# EvoProject_1_0_-_Entradas_e_Sa_das.net
KiCad netlist of a schematic drawn in Altium Designer
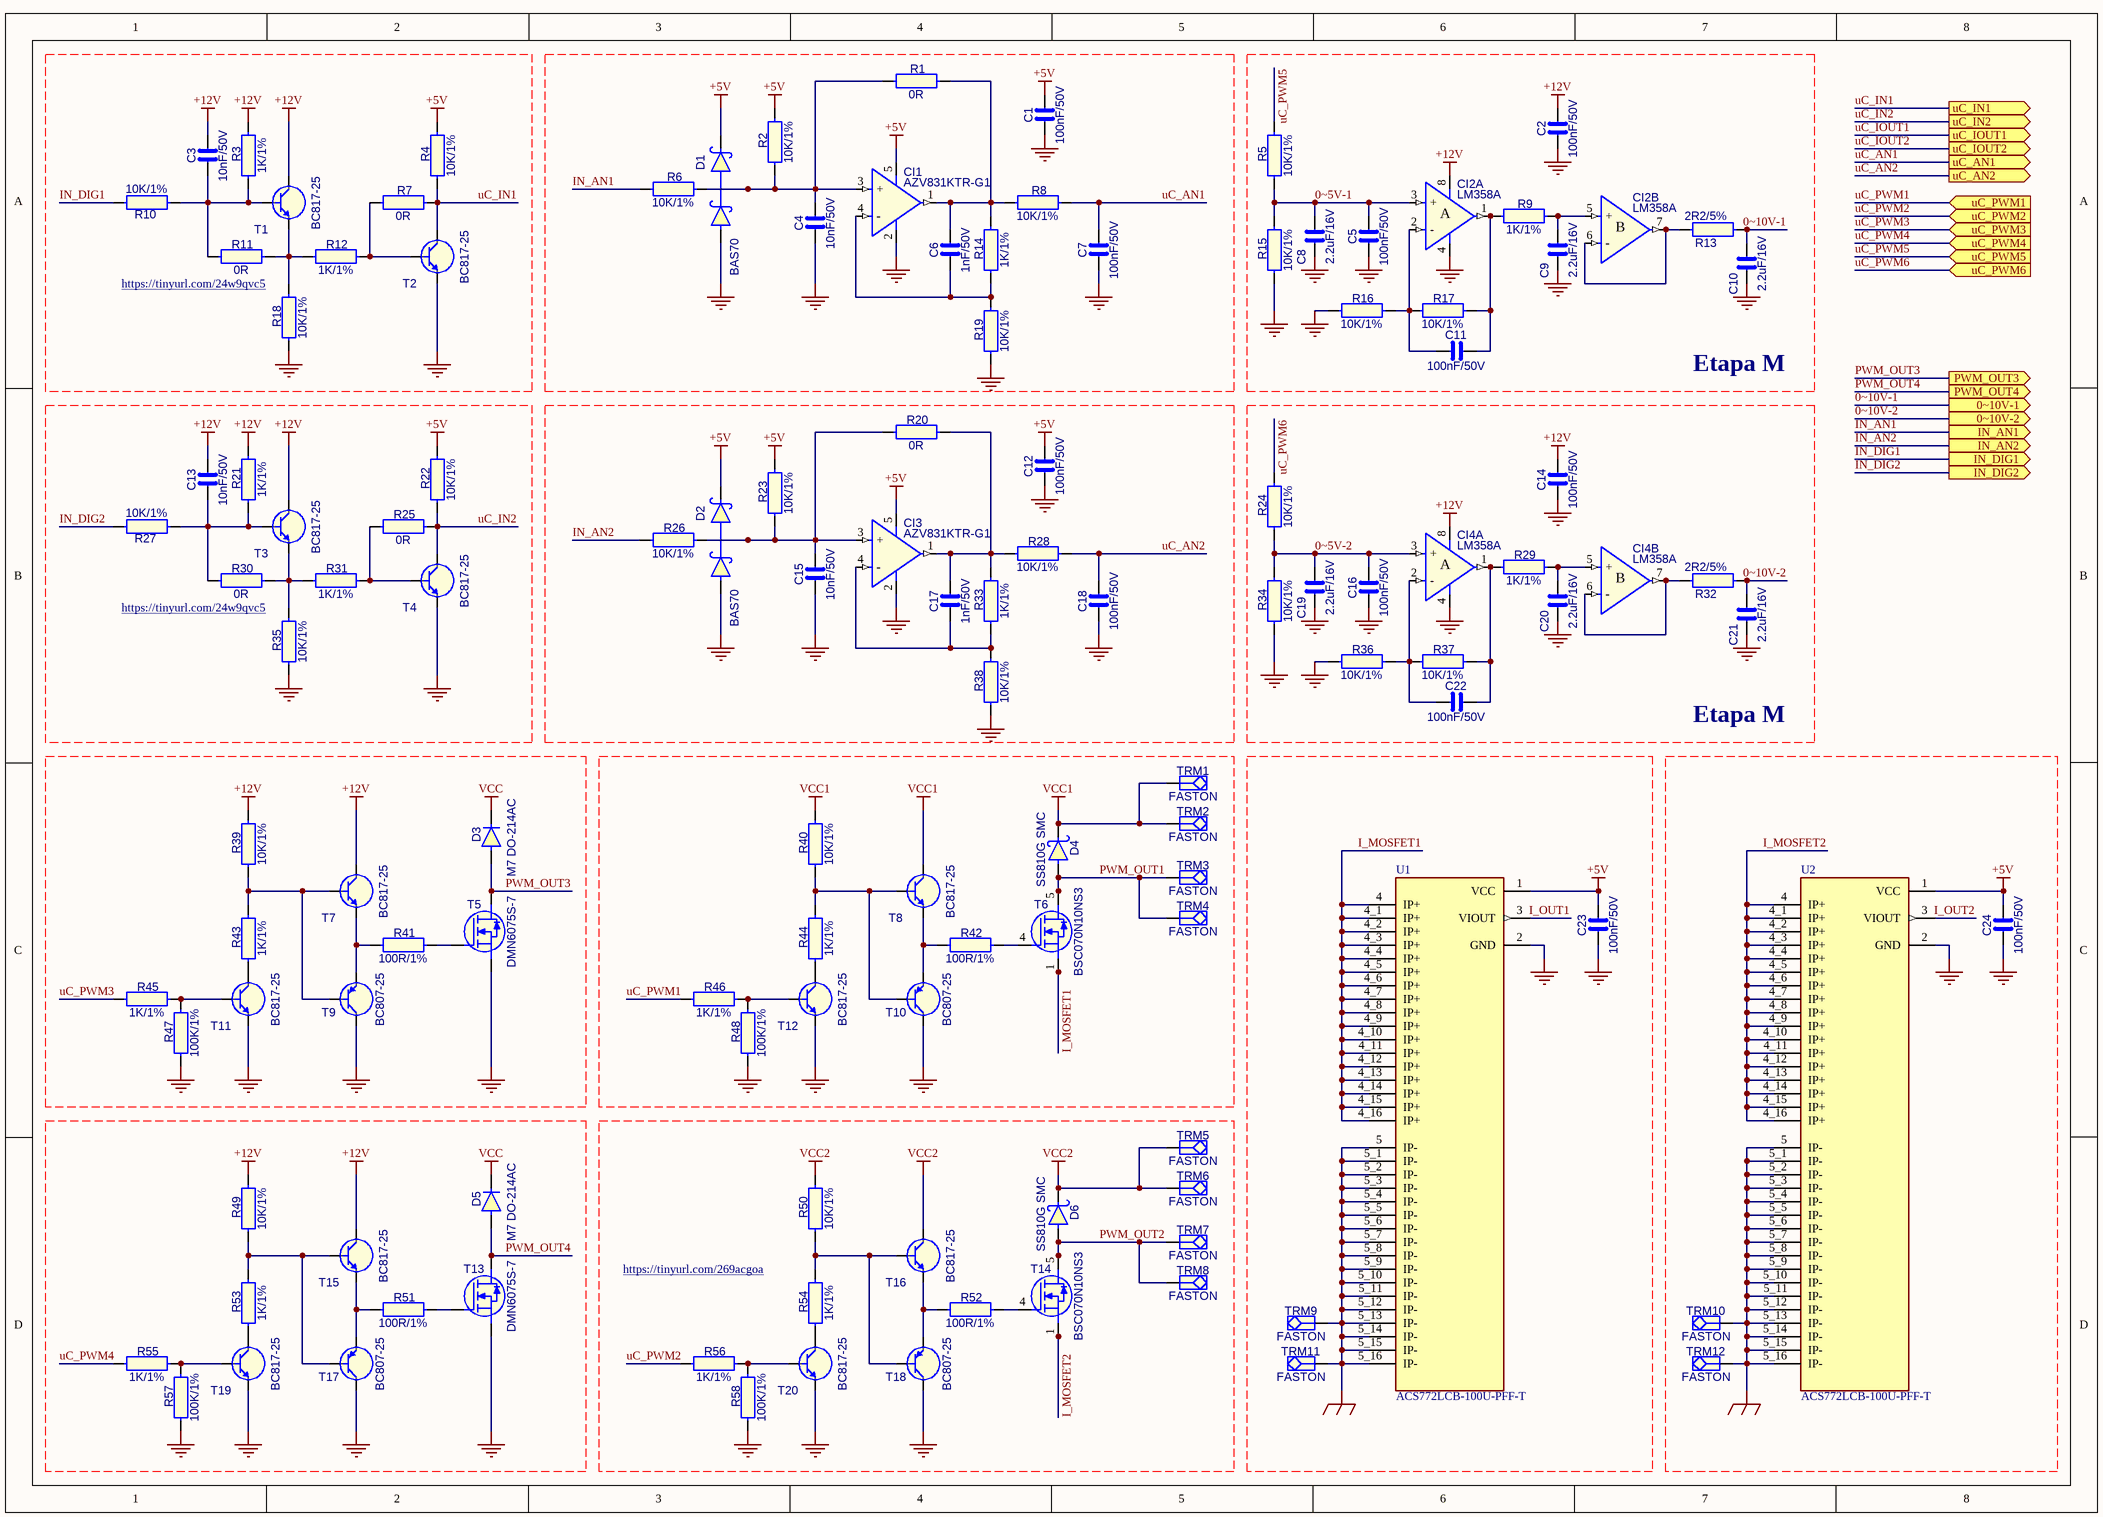
[diagram p0: EvoProject 1.0 - Entradas e Saídas.SchDoc]

(export (version "E")
  (design (tool "Eeschema 10.0.6"))
  (components
    (comp (ref "C1")
      (value "100nF/50V")
      (footprint "CAP SMD CE 0603 HR")
      (description "CAPACITOR SMD CE 0603 100nF 50V 10% X7R")
      (libsource (lib "INOVA SISTEMAS ELETRONICOS") (part "CAP_NP"))
    )
    (comp (ref "C2")
      (value "100nF/50V")
      (footprint "CAP SMD CE 0603 HR")
      (description "CAPACITOR SMD CE 0603 100nF 50V 10% X7R")
      (libsource (lib "INOVA SISTEMAS ELETRONICOS") (part "CAP_NP"))
    )
    (comp (ref "C3")
      (value "10nF/50V")
      (footprint "CAP SMD CE 0603 HR")
      (description "CAPACITOR SMD CE 0603 10nF 50V 20% X7R")
      (libsource (lib "INOVA SISTEMAS ELETRONICOS") (part "CAP_NP"))
    )
    (comp (ref "C4")
      (value "10nF/50V")
      (footprint "CAP SMD CE 0603 HR")
      (description "CAPACITOR SMD CE 0603 10nF 50V 20% X7R")
      (libsource (lib "INOVA SISTEMAS ELETRONICOS") (part "CAP_NP"))
    )
    (comp (ref "C5")
      (value "100nF/50V")
      (footprint "CAP SMD CE 0603 HR")
      (description "CAPACITOR SMD CE 0603 100nF 50V 10% X7R")
      (libsource (lib "INOVA SISTEMAS ELETRONICOS") (part "CAP_NP"))
    )
    (comp (ref "C6")
      (value "1nF/50V")
      (footprint "CAP SMD CE 0603 HR")
      (description "CAPACITOR SMD CE 0603 1nF 50V 10% X7R")
      (libsource (lib "INOVA SISTEMAS ELETRONICOS") (part "CAP_NP"))
    )
    (comp (ref "C7")
      (value "100nF/50V")
      (footprint "CAP SMD CE 0603 HR")
      (description "CAPACITOR SMD CE 0603 100nF 50V 10% X7R")
      (libsource (lib "INOVA SISTEMAS ELETRONICOS") (part "CAP_NP"))
    )
    (comp (ref "C8")
      (value "2.2uF/16V")
      (footprint "CAP SMD CE 0603 HR")
      (description "CAPACITOR SMD CE 0603 2,2uF 16V 10% X5R")
      (libsource (lib "INOVA SISTEMAS ELETRONICOS") (part "CAP_NP"))
    )
    (comp (ref "C9")
      (value "2.2uF/16V")
      (footprint "CAP SMD CE 0603 HR")
      (description "CAPACITOR SMD CE 0603 2,2uF 16V 10% X5R")
      (libsource (lib "INOVA SISTEMAS ELETRONICOS") (part "CAP_NP"))
    )
    (comp (ref "C10")
      (value "2.2uF/16V")
      (footprint "CAP SMD CE 0603 HR")
      (description "CAPACITOR SMD CE 0603 2,2uF 16V 10% X5R")
      (libsource (lib "INOVA SISTEMAS ELETRONICOS") (part "CAP_NP"))
    )
    (comp (ref "C11")
      (value "100nF/50V")
      (footprint "CAP SMD CE 0603 HR")
      (description "CAPACITOR SMD CE 0603 100nF 50V 10% X7R")
      (libsource (lib "INOVA SISTEMAS ELETRONICOS") (part "CAP_NP"))
    )
    (comp (ref "C12")
      (value "100nF/50V")
      (footprint "CAP SMD CE 0603 HR")
      (description "CAPACITOR SMD CE 0603 100nF 50V 10% X7R")
      (libsource (lib "INOVA SISTEMAS ELETRONICOS") (part "CAP_NP"))
    )
    (comp (ref "C13")
      (value "10nF/50V")
      (footprint "CAP SMD CE 0603 HR")
      (description "CAPACITOR SMD CE 0603 10nF 50V 20% X7R")
      (libsource (lib "INOVA SISTEMAS ELETRONICOS") (part "CAP_NP"))
    )
    (comp (ref "C14")
      (value "100nF/50V")
      (footprint "CAP SMD CE 0603 HR")
      (description "CAPACITOR SMD CE 0603 100nF 50V 10% X7R")
      (libsource (lib "INOVA SISTEMAS ELETRONICOS") (part "CAP_NP"))
    )
    (comp (ref "C15")
      (value "10nF/50V")
      (footprint "CAP SMD CE 0603 HR")
      (description "CAPACITOR SMD CE 0603 10nF 50V 20% X7R")
      (libsource (lib "INOVA SISTEMAS ELETRONICOS") (part "CAP_NP"))
    )
    (comp (ref "C16")
      (value "100nF/50V")
      (footprint "CAP SMD CE 0603 HR")
      (description "CAPACITOR SMD CE 0603 100nF 50V 10% X7R")
      (libsource (lib "INOVA SISTEMAS ELETRONICOS") (part "CAP_NP"))
    )
    (comp (ref "C17")
      (value "1nF/50V")
      (footprint "CAP SMD CE 0603 HR")
      (description "CAPACITOR SMD CE 0603 1nF 50V 10% X7R")
      (libsource (lib "INOVA SISTEMAS ELETRONICOS") (part "CAP_NP"))
    )
    (comp (ref "C18")
      (value "100nF/50V")
      (footprint "CAP SMD CE 0603 HR")
      (description "CAPACITOR SMD CE 0603 100nF 50V 10% X7R")
      (libsource (lib "INOVA SISTEMAS ELETRONICOS") (part "CAP_NP"))
    )
    (comp (ref "C19")
      (value "2.2uF/16V")
      (footprint "CAP SMD CE 0603 HR")
      (description "CAPACITOR SMD CE 0603 2,2uF 16V 10% X5R")
      (libsource (lib "INOVA SISTEMAS ELETRONICOS") (part "CAP_NP"))
    )
    (comp (ref "C20")
      (value "2.2uF/16V")
      (footprint "CAP SMD CE 0603 HR")
      (description "CAPACITOR SMD CE 0603 2,2uF 16V 10% X5R")
      (libsource (lib "INOVA SISTEMAS ELETRONICOS") (part "CAP_NP"))
    )
    (comp (ref "C21")
      (value "2.2uF/16V")
      (footprint "CAP SMD CE 0603 HR")
      (description "CAPACITOR SMD CE 0603 2,2uF 16V 10% X5R")
      (libsource (lib "INOVA SISTEMAS ELETRONICOS") (part "CAP_NP"))
    )
    (comp (ref "C22")
      (value "100nF/50V")
      (footprint "CAP SMD CE 0603 HR")
      (description "CAPACITOR SMD CE 0603 100nF 50V 10% X7R")
      (libsource (lib "INOVA SISTEMAS ELETRONICOS") (part "CAP_NP"))
    )
    (comp (ref "C23")
      (value "100nF/50V")
      (footprint "CAP SMD CE 0603 HR")
      (description "CAPACITOR SMD CE 0603 100nF 50V 10% X7R")
      (libsource (lib "INOVA SISTEMAS ELETRONICOS") (part "CAP_NP"))
    )
    (comp (ref "C24")
      (value "100nF/50V")
      (footprint "CAP SMD CE 0603 HR")
      (description "CAPACITOR SMD CE 0603 100nF 50V 10% X7R")
      (libsource (lib "INOVA SISTEMAS ELETRONICOS") (part "CAP_NP"))
    )
    (comp (ref "CI1")
      (value "AZV831KTR-G1")
      (footprint "GEN SMD SOT23-5 MR")
      (description "CI OP AZV831KTR-G1")
      (libsource (lib "INOVA SISTEMAS ELETRONICOS") (part "CI_OPA333"))
    )
    (comp (ref "CI2")
      (value "LM358A")
      (footprint "GEN SMD SOIC8 P.1,27 MR")
      (description "CI SMD LM 358")
      (libsource (lib "INOVA SISTEMAS ELETRONICOS") (part "CI_OPA2227"))
    )
    (comp (ref "CI3")
      (value "AZV831KTR-G1")
      (footprint "GEN SMD SOT23-5 MR")
      (description "CI OP AZV831KTR-G1")
      (libsource (lib "INOVA SISTEMAS ELETRONICOS") (part "CI_OPA333"))
    )
    (comp (ref "CI4")
      (value "LM358A")
      (footprint "GEN SMD SOIC8 P.1,27 MR")
      (description "CI SMD LM 358")
      (libsource (lib "INOVA SISTEMAS ELETRONICOS") (part "CI_OPA2227"))
    )
    (comp (ref "D1")
      (value "BAS70")
      (footprint "GEN SMD SOT23-3 TO-236AA MR")
      (description "DIODO SMD SCH SOT-23 70V 100mA")
      (libsource (lib "INOVA SISTEMAS ELETRONICOS") (part "DIO_Schottky Clamp"))
    )
    (comp (ref "D2")
      (value "BAS70")
      (footprint "GEN SMD SOT23-3 TO-236AA MR")
      (description "DIODO SMD SCH SOT-23 70V 100mA")
      (libsource (lib "INOVA SISTEMAS ELETRONICOS") (part "DIO_Schottky Clamp"))
    )
    (comp (ref "D3")
      (value "M7 DO-214AC")
      (footprint "DIO SMD SMA DO214AC MR")
      (description "DIODO SMD 1N4007 SMA")
      (libsource (lib "INOVA SISTEMAS ELETRONICOS") (part "DIO_Comum"))
    )
    (comp (ref "D4")
      (value "SS810G SMC")
      (footprint "DIO SMD SMC DO214AB HR")
      (description "DIODO SCHOTTKY SK810 SMD")
      (libsource (lib "INOVA SISTEMAS ELETRONICOS") (part "DIO_Schottky"))
    )
    (comp (ref "D5")
      (value "M7 DO-214AC")
      (footprint "DIO SMD SMA DO214AC MR")
      (description "DIODO SMD 1N4007 SMA")
      (libsource (lib "INOVA SISTEMAS ELETRONICOS") (part "DIO_Comum"))
    )
    (comp (ref "D6")
      (value "SS810G SMC")
      (footprint "DIO SMD SMC DO214AB HR")
      (description "DIODO SCHOTTKY SK810 SMD")
      (libsource (lib "INOVA SISTEMAS ELETRONICOS") (part "DIO_Schottky"))
    )
    (comp (ref "R1")
      (value "0R")
      (footprint "RES SMD CH 0603 HR")
      (description "RESISTOR SMD CH 0603 0R JMP 1/10W")
      (libsource (lib "") (part "RES_Geral_1"))
    )
    (comp (ref "R2")
      (value "10K/1%")
      (footprint "RES SMD CH 0603 HR")
      (description "RESISTOR SMD CH 0603 10K 1% 1/10W")
      (libsource (lib "INOVA SISTEMAS ELETRONICOS") (part "RES_Geral"))
    )
    (comp (ref "R3")
      (value "1K/1%")
      (footprint "RES SMD CH 0603 HR")
      (description "RESISTOR SMD CH 0603 1K 1% 1/10W")
      (libsource (lib "INOVA SISTEMAS ELETRONICOS") (part "RES_Geral"))
    )
    (comp (ref "R4")
      (value "10K/1%")
      (footprint "RES SMD CH 0603 HR")
      (description "RESISTOR SMD CH 0603 10K 1% 1/10W")
      (libsource (lib "INOVA SISTEMAS ELETRONICOS") (part "RES_Geral"))
    )
    (comp (ref "R5")
      (value "10K/1%")
      (footprint "RES SMD CH 0603 HR")
      (description "RESISTOR SMD CH 0603 10K 1% 1/10W")
      (libsource (lib "INOVA SISTEMAS ELETRONICOS") (part "RES_Geral"))
    )
    (comp (ref "R6")
      (value "10K/1%")
      (footprint "RES SMD CH 0603 HR")
      (description "RESISTOR SMD CH 0603 10K 1% 1/10W")
      (libsource (lib "") (part "RES_Geral_1"))
    )
    (comp (ref "R7")
      (value "0R")
      (footprint "RES SMD CH 0603 HR")
      (description "RESISTOR SMD CH 0603 0R JMP 1/10W")
      (libsource (lib "") (part "RES_Geral_1"))
    )
    (comp (ref "R8")
      (value "10K/1%")
      (footprint "RES SMD CH 0603 HR")
      (description "RESISTOR SMD CH 0603 10K 1% 1/10W")
      (libsource (lib "") (part "RES_Geral_1"))
    )
    (comp (ref "R9")
      (value "1K/1%")
      (footprint "RES SMD CH 0603 HR")
      (description "RESISTOR SMD CH 0603 1K 1% 1/10W")
      (libsource (lib "") (part "RES_Geral_1"))
    )
    (comp (ref "R10")
      (value "10K/1%")
      (footprint "RES SMD CH 0603 HR")
      (description "RESISTOR SMD CH 0603 10K 1% 1/10W")
      (libsource (lib "") (part "RES_Geral_2"))
    )
    (comp (ref "R11")
      (value "0R")
      (footprint "RES SMD CH 0603 HR")
      (description "RESISTOR SMD CH 0603 0R JMP 1/10W")
      (libsource (lib "") (part "RES_Geral_1"))
    )
    (comp (ref "R12")
      (value "1K/1%")
      (footprint "RES SMD CH 0603 HR")
      (description "RESISTOR SMD CH 0603 1K 1% 1/10W")
      (libsource (lib "") (part "RES_Geral_1"))
    )
    (comp (ref "R13")
      (value "2R2/5%")
      (footprint "RES SMD CH 0603 HR")
      (description "RESISTOR SMD CH 0603 2R2 5% 1/10W")
      (libsource (lib "") (part "RES_Geral_2"))
    )
    (comp (ref "R14")
      (value "1K/1%")
      (footprint "RES SMD CH 0603 HR")
      (description "RESISTOR SMD CH 0603 1K 1% 1/10W")
      (libsource (lib "INOVA SISTEMAS ELETRONICOS") (part "RES_Geral"))
    )
    (comp (ref "R15")
      (value "10K/1%")
      (footprint "RES SMD CH 0603 HR")
      (description "RESISTOR SMD CH 0603 10K 1% 1/10W")
      (libsource (lib "INOVA SISTEMAS ELETRONICOS") (part "RES_Geral"))
    )
    (comp (ref "R16")
      (value "10K/1%")
      (footprint "RES SMD CH 0603 HR")
      (description "RESISTOR SMD CH 0603 10K 1% 1/10W")
      (libsource (lib "") (part "RES_Geral_1"))
    )
    (comp (ref "R17")
      (value "10K/1%")
      (footprint "RES SMD CH 0603 HR")
      (description "RESISTOR SMD CH 0603 10K 1% 1/10W")
      (libsource (lib "") (part "RES_Geral_1"))
    )
    (comp (ref "R18")
      (value "10K/1%")
      (footprint "RES SMD CH 0603 HR")
      (description "RESISTOR SMD CH 0603 10K 1% 1/10W")
      (libsource (lib "INOVA SISTEMAS ELETRONICOS") (part "RES_Geral"))
    )
    (comp (ref "R19")
      (value "10K/1%")
      (footprint "RES SMD CH 0603 HR")
      (description "RESISTOR SMD CH 0603 10K 1% 1/10W")
      (libsource (lib "INOVA SISTEMAS ELETRONICOS") (part "RES_Geral"))
    )
    (comp (ref "R20")
      (value "0R")
      (footprint "RES SMD CH 0603 HR")
      (description "RESISTOR SMD CH 0603 0R JMP 1/10W")
      (libsource (lib "") (part "RES_Geral_1"))
    )
    (comp (ref "R21")
      (value "1K/1%")
      (footprint "RES SMD CH 0603 HR")
      (description "RESISTOR SMD CH 0603 1K 1% 1/10W")
      (libsource (lib "INOVA SISTEMAS ELETRONICOS") (part "RES_Geral"))
    )
    (comp (ref "R22")
      (value "10K/1%")
      (footprint "RES SMD CH 0603 HR")
      (description "RESISTOR SMD CH 0603 10K 1% 1/10W")
      (libsource (lib "INOVA SISTEMAS ELETRONICOS") (part "RES_Geral"))
    )
    (comp (ref "R23")
      (value "10K/1%")
      (footprint "RES SMD CH 0603 HR")
      (description "RESISTOR SMD CH 0603 10K 1% 1/10W")
      (libsource (lib "INOVA SISTEMAS ELETRONICOS") (part "RES_Geral"))
    )
    (comp (ref "R24")
      (value "10K/1%")
      (footprint "RES SMD CH 0603 HR")
      (description "RESISTOR SMD CH 0603 10K 1% 1/10W")
      (libsource (lib "INOVA SISTEMAS ELETRONICOS") (part "RES_Geral"))
    )
    (comp (ref "R25")
      (value "0R")
      (footprint "RES SMD CH 0603 HR")
      (description "RESISTOR SMD CH 0603 0R JMP 1/10W")
      (libsource (lib "") (part "RES_Geral_1"))
    )
    (comp (ref "R26")
      (value "10K/1%")
      (footprint "RES SMD CH 0603 HR")
      (description "RESISTOR SMD CH 0603 10K 1% 1/10W")
      (libsource (lib "") (part "RES_Geral_1"))
    )
    (comp (ref "R27")
      (value "10K/1%")
      (footprint "RES SMD CH 0603 HR")
      (description "RESISTOR SMD CH 0603 10K 1% 1/10W")
      (libsource (lib "") (part "RES_Geral_2"))
    )
    (comp (ref "R28")
      (value "10K/1%")
      (footprint "RES SMD CH 0603 HR")
      (description "RESISTOR SMD CH 0603 10K 1% 1/10W")
      (libsource (lib "") (part "RES_Geral_1"))
    )
    (comp (ref "R29")
      (value "1K/1%")
      (footprint "RES SMD CH 0603 HR")
      (description "RESISTOR SMD CH 0603 1K 1% 1/10W")
      (libsource (lib "") (part "RES_Geral_1"))
    )
    (comp (ref "R30")
      (value "0R")
      (footprint "RES SMD CH 0603 HR")
      (description "RESISTOR SMD CH 0603 0R JMP 1/10W")
      (libsource (lib "") (part "RES_Geral_1"))
    )
    (comp (ref "R31")
      (value "1K/1%")
      (footprint "RES SMD CH 0603 HR")
      (description "RESISTOR SMD CH 0603 1K 1% 1/10W")
      (libsource (lib "") (part "RES_Geral_1"))
    )
    (comp (ref "R32")
      (value "2R2/5%")
      (footprint "RES SMD CH 0603 HR")
      (description "RESISTOR SMD CH 0603 2R2 5% 1/10W")
      (libsource (lib "") (part "RES_Geral_2"))
    )
    (comp (ref "R33")
      (value "1K/1%")
      (footprint "RES SMD CH 0603 HR")
      (description "RESISTOR SMD CH 0603 1K 1% 1/10W")
      (libsource (lib "INOVA SISTEMAS ELETRONICOS") (part "RES_Geral"))
    )
    (comp (ref "R34")
      (value "10K/1%")
      (footprint "RES SMD CH 0603 HR")
      (description "RESISTOR SMD CH 0603 10K 1% 1/10W")
      (libsource (lib "INOVA SISTEMAS ELETRONICOS") (part "RES_Geral"))
    )
    (comp (ref "R35")
      (value "10K/1%")
      (footprint "RES SMD CH 0603 HR")
      (description "RESISTOR SMD CH 0603 10K 1% 1/10W")
      (libsource (lib "INOVA SISTEMAS ELETRONICOS") (part "RES_Geral"))
    )
    (comp (ref "R36")
      (value "10K/1%")
      (footprint "RES SMD CH 0603 HR")
      (description "RESISTOR SMD CH 0603 10K 1% 1/10W")
      (libsource (lib "") (part "RES_Geral_1"))
    )
    (comp (ref "R37")
      (value "10K/1%")
      (footprint "RES SMD CH 0603 HR")
      (description "RESISTOR SMD CH 0603 10K 1% 1/10W")
      (libsource (lib "") (part "RES_Geral_1"))
    )
    (comp (ref "R38")
      (value "10K/1%")
      (footprint "RES SMD CH 0603 HR")
      (description "RESISTOR SMD CH 0603 10K 1% 1/10W")
      (libsource (lib "INOVA SISTEMAS ELETRONICOS") (part "RES_Geral"))
    )
    (comp (ref "R39")
      (value "10K/1%")
      (footprint "RES SMD CH 0603 HR")
      (description "RESISTOR SMD CH 0603 10K 1% 1/10W")
      (libsource (lib "INOVA SISTEMAS ELETRONICOS") (part "RES_Geral"))
    )
    (comp (ref "R40")
      (value "10K/1%")
      (footprint "RES SMD CH 0603 HR")
      (description "RESISTOR SMD CH 0603 10K 1% 1/10W")
      (libsource (lib "INOVA SISTEMAS ELETRONICOS") (part "RES_Geral"))
    )
    (comp (ref "R41")
      (value "100R/1%")
      (footprint "RES SMD CH 0603 HR")
      (description "RESISTOR SMD CH 0603 100R 1% 1/10W")
      (libsource (lib "") (part "RES_Geral_1"))
    )
    (comp (ref "R42")
      (value "100R/1%")
      (footprint "RES SMD CH 0603 HR")
      (description "RESISTOR SMD CH 0603 100R 1% 1/10W")
      (libsource (lib "") (part "RES_Geral_1"))
    )
    (comp (ref "R43")
      (value "1K/1%")
      (footprint "RES SMD CH 0603 HR")
      (description "RESISTOR SMD CH 0603 1K 1% 1/10W")
      (libsource (lib "INOVA SISTEMAS ELETRONICOS") (part "RES_Geral"))
    )
    (comp (ref "R44")
      (value "1K/1%")
      (footprint "RES SMD CH 0603 HR")
      (description "RESISTOR SMD CH 0603 1K 1% 1/10W")
      (libsource (lib "INOVA SISTEMAS ELETRONICOS") (part "RES_Geral"))
    )
    (comp (ref "R45")
      (value "1K/1%")
      (footprint "RES SMD CH 0603 HR")
      (description "RESISTOR SMD CH 0603 1K 1% 1/10W")
      (libsource (lib "") (part "RES_Geral_1"))
    )
    (comp (ref "R46")
      (value "1K/1%")
      (footprint "RES SMD CH 0603 HR")
      (description "RESISTOR SMD CH 0603 1K 1% 1/10W")
      (libsource (lib "") (part "RES_Geral_1"))
    )
    (comp (ref "R47")
      (value "100K/1%")
      (footprint "RES SMD CH 0603 HR")
      (description "RESISTOR SMD CH 0603 100K 1% 1/10W")
      (libsource (lib "INOVA SISTEMAS ELETRONICOS") (part "RES_Geral"))
    )
    (comp (ref "R48")
      (value "100K/1%")
      (footprint "RES SMD CH 0603 HR")
      (description "RESISTOR SMD CH 0603 100K 1% 1/10W")
      (libsource (lib "INOVA SISTEMAS ELETRONICOS") (part "RES_Geral"))
    )
    (comp (ref "R49")
      (value "10K/1%")
      (footprint "RES SMD CH 0603 HR")
      (description "RESISTOR SMD CH 0603 10K 1% 1/10W")
      (libsource (lib "INOVA SISTEMAS ELETRONICOS") (part "RES_Geral"))
    )
    (comp (ref "R50")
      (value "10K/1%")
      (footprint "RES SMD CH 0603 HR")
      (description "RESISTOR SMD CH 0603 10K 1% 1/10W")
      (libsource (lib "INOVA SISTEMAS ELETRONICOS") (part "RES_Geral"))
    )
    (comp (ref "R51")
      (value "100R/1%")
      (footprint "RES SMD CH 0603 HR")
      (description "RESISTOR SMD CH 0603 100R 1% 1/10W")
      (libsource (lib "") (part "RES_Geral_1"))
    )
    (comp (ref "R52")
      (value "100R/1%")
      (footprint "RES SMD CH 0603 HR")
      (description "RESISTOR SMD CH 0603 100R 1% 1/10W")
      (libsource (lib "") (part "RES_Geral_1"))
    )
    (comp (ref "R53")
      (value "1K/1%")
      (footprint "RES SMD CH 0603 HR")
      (description "RESISTOR SMD CH 0603 1K 1% 1/10W")
      (libsource (lib "INOVA SISTEMAS ELETRONICOS") (part "RES_Geral"))
    )
    (comp (ref "R54")
      (value "1K/1%")
      (footprint "RES SMD CH 0603 HR")
      (description "RESISTOR SMD CH 0603 1K 1% 1/10W")
      (libsource (lib "INOVA SISTEMAS ELETRONICOS") (part "RES_Geral"))
    )
    (comp (ref "R55")
      (value "1K/1%")
      (footprint "RES SMD CH 0603 HR")
      (description "RESISTOR SMD CH 0603 1K 1% 1/10W")
      (libsource (lib "") (part "RES_Geral_1"))
    )
    (comp (ref "R56")
      (value "1K/1%")
      (footprint "RES SMD CH 0603 HR")
      (description "RESISTOR SMD CH 0603 1K 1% 1/10W")
      (libsource (lib "") (part "RES_Geral_1"))
    )
    (comp (ref "R57")
      (value "100K/1%")
      (footprint "RES SMD CH 0603 HR")
      (description "RESISTOR SMD CH 0603 100K 1% 1/10W")
      (libsource (lib "INOVA SISTEMAS ELETRONICOS") (part "RES_Geral"))
    )
    (comp (ref "R58")
      (value "100K/1%")
      (footprint "RES SMD CH 0603 HR")
      (description "RESISTOR SMD CH 0603 100K 1% 1/10W")
      (libsource (lib "INOVA SISTEMAS ELETRONICOS") (part "RES_Geral"))
    )
    (comp (ref "T1")
      (value "BC817-25")
      (footprint "GEN SMD SOT23-3 TO-236AA MR")
      (description "TRANSISTOR SMD 817/25")
      (libsource (lib "INOVA SISTEMAS ELETRONICOS") (part "TRA_NPN SOT-23-3L"))
    )
    (comp (ref "T2")
      (value "BC817-25")
      (footprint "GEN SMD SOT23-3 TO-236AA MR")
      (description "TRANSISTOR SMD 817/25")
      (libsource (lib "INOVA SISTEMAS ELETRONICOS") (part "TRA_NPN SOT-23-3L"))
    )
    (comp (ref "T3")
      (value "BC817-25")
      (footprint "GEN SMD SOT23-3 TO-236AA MR")
      (description "TRANSISTOR SMD 817/25")
      (libsource (lib "INOVA SISTEMAS ELETRONICOS") (part "TRA_NPN SOT-23-3L"))
    )
    (comp (ref "T4")
      (value "BC817-25")
      (footprint "GEN SMD SOT23-3 TO-236AA MR")
      (description "TRANSISTOR SMD 817/25")
      (libsource (lib "INOVA SISTEMAS ELETRONICOS") (part "TRA_NPN SOT-23-3L"))
    )
    (comp (ref "T5")
      (value "DMN6075S-7")
      (footprint "GEN SMD SOT23-3 TO-236AA HR")
      (description "TRANSISTOR MOSFET DMN6075S SMD")
      (libsource (lib "INOVA SISTEMAS ELETRONICOS") (part "TRA_MOSFET_N-SOT23-3L"))
    )
    (comp (ref "T6")
      (value "BSC070N10NS3")
      (footprint "GEN SMD PG-TDSON-8 MR")
      (description "MOSFET SMD N-CH TDSON-8 100V 90A 114W 7mOhm")
      (libsource (lib "INOVA SISTEMAS ELETRONICOS") (part "TRA_MOSFET_N-POWERPAK-SO8"))
    )
    (comp (ref "T7")
      (value "BC817-25")
      (footprint "GEN SMD SOT23-3 TO-236AA MR")
      (description "TRANSISTOR SMD 817/25")
      (libsource (lib "INOVA SISTEMAS ELETRONICOS") (part "TRA_NPN SOT-23-3L"))
    )
    (comp (ref "T8")
      (value "BC817-25")
      (footprint "GEN SMD SOT23-3 TO-236AA MR")
      (description "TRANSISTOR SMD 817/25")
      (libsource (lib "INOVA SISTEMAS ELETRONICOS") (part "TRA_NPN SOT-23-3L"))
    )
    (comp (ref "T9")
      (value "BC807-25")
      (footprint "GEN SMD SOT23-3 TO-236AA MR")
      (description "TRANSISTOR SMD 807/25")
      (libsource (lib "INOVA SISTEMAS ELETRONICOS") (part "TRA_PNP SOT-23-3L"))
    )
    (comp (ref "T10")
      (value "BC807-25")
      (footprint "GEN SMD SOT23-3 TO-236AA MR")
      (description "TRANSISTOR SMD 807/25")
      (libsource (lib "INOVA SISTEMAS ELETRONICOS") (part "TRA_PNP SOT-23-3L"))
    )
    (comp (ref "T11")
      (value "BC817-25")
      (footprint "GEN SMD SOT23-3 TO-236AA MR")
      (description "TRANSISTOR SMD 817/25")
      (libsource (lib "INOVA SISTEMAS ELETRONICOS") (part "TRA_NPN SOT-23-3L"))
    )
    (comp (ref "T12")
      (value "BC817-25")
      (footprint "GEN SMD SOT23-3 TO-236AA MR")
      (description "TRANSISTOR SMD 817/25")
      (libsource (lib "INOVA SISTEMAS ELETRONICOS") (part "TRA_NPN SOT-23-3L"))
    )
    (comp (ref "T13")
      (value "DMN6075S-7")
      (footprint "GEN SMD SOT23-3 TO-236AA HR")
      (description "TRANSISTOR MOSFET DMN6075S SMD")
      (libsource (lib "INOVA SISTEMAS ELETRONICOS") (part "TRA_MOSFET_N-SOT23-3L"))
    )
    (comp (ref "T14")
      (value "BSC070N10NS3")
      (footprint "GEN SMD PG-TDSON-8 MR")
      (description "MOSFET SMD N-CH TDSON-8 100V 90A 114W 7mOhm")
      (libsource (lib "INOVA SISTEMAS ELETRONICOS") (part "TRA_MOSFET_N-POWERPAK-SO8"))
    )
    (comp (ref "T15")
      (value "BC817-25")
      (footprint "GEN SMD SOT23-3 TO-236AA MR")
      (description "TRANSISTOR SMD 817/25")
      (libsource (lib "INOVA SISTEMAS ELETRONICOS") (part "TRA_NPN SOT-23-3L"))
    )
    (comp (ref "T16")
      (value "BC817-25")
      (footprint "GEN SMD SOT23-3 TO-236AA MR")
      (description "TRANSISTOR SMD 817/25")
      (libsource (lib "INOVA SISTEMAS ELETRONICOS") (part "TRA_NPN SOT-23-3L"))
    )
    (comp (ref "T17")
      (value "BC807-25")
      (footprint "GEN SMD SOT23-3 TO-236AA MR")
      (description "TRANSISTOR SMD 807/25")
      (libsource (lib "INOVA SISTEMAS ELETRONICOS") (part "TRA_PNP SOT-23-3L"))
    )
    (comp (ref "T18")
      (value "BC807-25")
      (footprint "GEN SMD SOT23-3 TO-236AA MR")
      (description "TRANSISTOR SMD 807/25")
      (libsource (lib "INOVA SISTEMAS ELETRONICOS") (part "TRA_PNP SOT-23-3L"))
    )
    (comp (ref "T19")
      (value "BC817-25")
      (footprint "GEN SMD SOT23-3 TO-236AA MR")
      (description "TRANSISTOR SMD 817/25")
      (libsource (lib "INOVA SISTEMAS ELETRONICOS") (part "TRA_NPN SOT-23-3L"))
    )
    (comp (ref "T20")
      (value "BC817-25")
      (footprint "GEN SMD SOT23-3 TO-236AA MR")
      (description "TRANSISTOR SMD 817/25")
      (libsource (lib "INOVA SISTEMAS ELETRONICOS") (part "TRA_NPN SOT-23-3L"))
    )
    (comp (ref "TRM1")
      (value "FASTON")
      (footprint "Terminal Faston Macho 180° OBLONGO COM SUPORTE")
      (description "TERMINAL P/ PCI 180° 6,35mmX14,2mm BAIONETA")
      (libsource (lib "INOVA SISTEMAS ELETRONICOS") (part "CON_TERMINAL"))
    )
    (comp (ref "TRM2")
      (value "FASTON")
      (footprint "Terminal Faston Macho 180° OBLONGO COM SUPORTE")
      (description "TERMINAL P/ PCI 180° 6,35mmX14,2mm BAIONETA")
      (libsource (lib "INOVA SISTEMAS ELETRONICOS") (part "CON_TERMINAL"))
    )
    (comp (ref "TRM3")
      (value "FASTON")
      (footprint "Terminal Faston Macho 180° OBLONGO COM SUPORTE")
      (description "TERMINAL P/ PCI 180° 6,35mmX14,2mm BAIONETA")
      (libsource (lib "INOVA SISTEMAS ELETRONICOS") (part "CON_TERMINAL"))
    )
    (comp (ref "TRM4")
      (value "FASTON")
      (footprint "Terminal Faston Macho 180° OBLONGO COM SUPORTE")
      (description "TERMINAL P/ PCI 180° 6,35mmX14,2mm BAIONETA")
      (libsource (lib "INOVA SISTEMAS ELETRONICOS") (part "CON_TERMINAL"))
    )
    (comp (ref "TRM5")
      (value "FASTON")
      (footprint "Terminal Faston Macho 180° OBLONGO COM SUPORTE")
      (description "TERMINAL P/ PCI 180° 6,35mmX14,2mm BAIONETA")
      (libsource (lib "INOVA SISTEMAS ELETRONICOS") (part "CON_TERMINAL"))
    )
    (comp (ref "TRM6")
      (value "FASTON")
      (footprint "Terminal Faston Macho 180° OBLONGO COM SUPORTE")
      (description "TERMINAL P/ PCI 180° 6,35mmX14,2mm BAIONETA")
      (libsource (lib "INOVA SISTEMAS ELETRONICOS") (part "CON_TERMINAL"))
    )
    (comp (ref "TRM7")
      (value "FASTON")
      (footprint "Terminal Faston Macho 180° OBLONGO COM SUPORTE")
      (description "TERMINAL P/ PCI 180° 6,35mmX14,2mm BAIONETA")
      (libsource (lib "INOVA SISTEMAS ELETRONICOS") (part "CON_TERMINAL"))
    )
    (comp (ref "TRM8")
      (value "FASTON")
      (footprint "Terminal Faston Macho 180° OBLONGO COM SUPORTE")
      (description "TERMINAL P/ PCI 180° 6,35mmX14,2mm BAIONETA")
      (libsource (lib "INOVA SISTEMAS ELETRONICOS") (part "CON_TERMINAL"))
    )
    (comp (ref "TRM9")
      (value "FASTON")
      (footprint "Terminal Faston Macho 180° OBLONGO COM SUPORTE")
      (description "TERMINAL P/ PCI 180° 6,35mmX14,2mm BAIONETA")
      (libsource (lib "") (part "CON_TERMINAL_1"))
    )
    (comp (ref "TRM10")
      (value "FASTON")
      (footprint "Terminal Faston Macho 180° OBLONGO COM SUPORTE")
      (description "TERMINAL P/ PCI 180° 6,35mmX14,2mm BAIONETA")
      (libsource (lib "") (part "CON_TERMINAL_1"))
    )
    (comp (ref "TRM11")
      (value "FASTON")
      (footprint "Terminal Faston Macho 180° OBLONGO COM SUPORTE")
      (description "TERMINAL P/ PCI 180° 6,35mmX14,2mm BAIONETA")
      (libsource (lib "") (part "CON_TERMINAL_1"))
    )
    (comp (ref "TRM12")
      (value "FASTON")
      (footprint "Terminal Faston Macho 180° OBLONGO COM SUPORTE")
      (description "TERMINAL P/ PCI 180° 6,35mmX14,2mm BAIONETA")
      (libsource (lib "") (part "CON_TERMINAL_1"))
    )
    (comp (ref "U1")
      (value "ACS772LCB-100U-PFF-T")
      (footprint "XDCR_ACS772LCB-100U-PFF-T")
      (description "Current Sensor 100A 1 Channel Hall Effect Unidirectional 5-CB Formed Leads, PFF")
      (fields (field (name "MF") "Allegro MicroSystems LLC"))
      (libsource (lib "ACS772LCB-100U-PFF-T") (part "ACS772LCB-100U-PFF-T"))
    )
    (comp (ref "U2")
      (value "ACS772LCB-100U-PFF-T")
      (footprint "XDCR_ACS772LCB-100U-PFF-T")
      (description "Current Sensor 100A 1 Channel Hall Effect Unidirectional 5-CB Formed Leads, PFF")
      (fields (field (name "MF") "Allegro MicroSystems LLC"))
      (libsource (lib "ACS772LCB-100U-PFF-T") (part "ACS772LCB-100U-PFF-T"))
    )
  )
  (nets
    (net (code "1") (name "+5V") (class "Default")
      (node (ref "C1") (pin "1") (pinfunction "1_1") (pintype "passive"))
      (node (ref "C12") (pin "1") (pinfunction "1_1") (pintype "passive"))
      (node (ref "C23") (pin "1") (pinfunction "1_1") (pintype "passive"))
      (node (ref "C24") (pin "1") (pinfunction "1_1") (pintype "passive"))
      (node (ref "CI1") (pin "5") (pinfunction "VCC_5") (pintype "power_in"))
      (node (ref "CI3") (pin "5") (pinfunction "VCC_5") (pintype "power_in"))
      (node (ref "D1") (pin "2") (pinfunction "K_2") (pintype "passive"))
      (node (ref "D2") (pin "2") (pinfunction "K_2") (pintype "passive"))
      (node (ref "R2") (pin "2") (pinfunction "2_2") (pintype "passive"))
      (node (ref "R22") (pin "2") (pinfunction "2_2") (pintype "passive"))
      (node (ref "R23") (pin "2") (pinfunction "2_2") (pintype "passive"))
      (node (ref "R4") (pin "2") (pinfunction "2_2") (pintype "passive"))
      (node (ref "U1") (pin "1") (pinfunction "VCC_1") (pintype "power_in"))
      (node (ref "U2") (pin "1") (pinfunction "VCC_1") (pintype "power_in"))
    )
    (net (code "2") (name "+12V") (class "Default")
      (node (ref "C13") (pin "1") (pinfunction "1_1") (pintype "passive"))
      (node (ref "C14") (pin "1") (pinfunction "1_1") (pintype "passive"))
      (node (ref "C2") (pin "1") (pinfunction "1_1") (pintype "passive"))
      (node (ref "C3") (pin "1") (pinfunction "1_1") (pintype "passive"))
      (node (ref "CI2") (pin "8") (pinfunction "VCC_8") (pintype "power_in"))
      (node (ref "CI4") (pin "8") (pinfunction "VCC_8") (pintype "power_in"))
      (node (ref "R21") (pin "2") (pinfunction "2_2") (pintype "passive"))
      (node (ref "R3") (pin "2") (pinfunction "2_2") (pintype "passive"))
      (node (ref "R39") (pin "2") (pinfunction "2_2") (pintype "passive"))
      (node (ref "R49") (pin "2") (pinfunction "2_2") (pintype "passive"))
      (node (ref "T1") (pin "3") (pinfunction "C_3") (pintype "passive"))
      (node (ref "T15") (pin "3") (pinfunction "C_3") (pintype "passive"))
      (node (ref "T3") (pin "3") (pinfunction "C_3") (pintype "passive"))
      (node (ref "T7") (pin "3") (pinfunction "C_3") (pintype "passive"))
    )
    (net (code "3") (name "/0~5V-1") (class "Default")
      (node (ref "C5") (pin "1") (pinfunction "1_1") (pintype "passive"))
      (node (ref "C8") (pin "1") (pinfunction "1_1") (pintype "passive"))
      (node (ref "CI2") (pin "3") (pinfunction "+_3") (pintype "input"))
      (node (ref "R15") (pin "2") (pinfunction "2_2") (pintype "passive"))
      (node (ref "R5") (pin "1") (pinfunction "1_1") (pintype "passive"))
    )
    (net (code "4") (name "/0~5V-2") (class "Default")
      (node (ref "C16") (pin "1") (pinfunction "1_1") (pintype "passive"))
      (node (ref "C19") (pin "1") (pinfunction "1_1") (pintype "passive"))
      (node (ref "CI4") (pin "3") (pinfunction "+_3") (pintype "input"))
      (node (ref "R24") (pin "1") (pinfunction "1_1") (pintype "passive"))
      (node (ref "R34") (pin "2") (pinfunction "2_2") (pintype "passive"))
    )
    (net (code "5") (name "/0~10V-1") (class "Default")
      (node (ref "C10") (pin "1") (pinfunction "1_1") (pintype "passive"))
      (node (ref "R13") (pin "1") (pinfunction "1_1") (pintype "passive"))
    )
    (net (code "6") (name "/0~10V-2") (class "Default")
      (node (ref "C21") (pin "1") (pinfunction "1_1") (pintype "passive"))
      (node (ref "R32") (pin "1") (pinfunction "1_1") (pintype "passive"))
    )
    (net (code "7") (name "/IN_AN1") (class "Default")
      (node (ref "R6") (pin "1") (pinfunction "1_1") (pintype "passive"))
    )
    (net (code "8") (name "/IN_AN2") (class "Default")
      (node (ref "R26") (pin "1") (pinfunction "1_1") (pintype "passive"))
    )
    (net (code "9") (name "/IN_DIG1") (class "Default")
      (node (ref "R10") (pin "2") (pinfunction "2_2") (pintype "passive"))
    )
    (net (code "10") (name "/IN_DIG2") (class "Default")
      (node (ref "R27") (pin "2") (pinfunction "2_2") (pintype "passive"))
    )
    (net (code "11") (name "/I_MOSFET1") (class "Default")
      (node (ref "T6") (pin "1") (pinfunction "S_1") (pintype "passive"))
      (node (ref "T6") (pin "2") (pinfunction "S_2") (pintype "passive"))
      (node (ref "T6") (pin "3") (pinfunction "S_3") (pintype "passive"))
      (node (ref "U1") (pin "4") (pinfunction "IP+_4") (pintype "passive"))
      (node (ref "U1") (pin "4_1") (pinfunction "IP+_4_1") (pintype "passive"))
      (node (ref "U1") (pin "4_10") (pinfunction "IP+_4_10") (pintype "passive"))
      (node (ref "U1") (pin "4_11") (pinfunction "IP+_4_11") (pintype "passive"))
      (node (ref "U1") (pin "4_12") (pinfunction "IP+_4_12") (pintype "passive"))
      (node (ref "U1") (pin "4_13") (pinfunction "IP+_4_13") (pintype "passive"))
      (node (ref "U1") (pin "4_14") (pinfunction "IP+_4_14") (pintype "passive"))
      (node (ref "U1") (pin "4_15") (pinfunction "IP+_4_15") (pintype "passive"))
      (node (ref "U1") (pin "4_16") (pinfunction "IP+_4_16") (pintype "passive"))
      (node (ref "U1") (pin "4_2") (pinfunction "IP+_4_2") (pintype "passive"))
      (node (ref "U1") (pin "4_3") (pinfunction "IP+_4_3") (pintype "passive"))
      (node (ref "U1") (pin "4_4") (pinfunction "IP+_4_4") (pintype "passive"))
      (node (ref "U1") (pin "4_5") (pinfunction "IP+_4_5") (pintype "passive"))
      (node (ref "U1") (pin "4_6") (pinfunction "IP+_4_6") (pintype "passive"))
      (node (ref "U1") (pin "4_7") (pinfunction "IP+_4_7") (pintype "passive"))
      (node (ref "U1") (pin "4_8") (pinfunction "IP+_4_8") (pintype "passive"))
      (node (ref "U1") (pin "4_9") (pinfunction "IP+_4_9") (pintype "passive"))
    )
    (net (code "12") (name "/I_MOSFET2") (class "Default")
      (node (ref "T14") (pin "1") (pinfunction "S_1") (pintype "passive"))
      (node (ref "T14") (pin "2") (pinfunction "S_2") (pintype "passive"))
      (node (ref "T14") (pin "3") (pinfunction "S_3") (pintype "passive"))
      (node (ref "U2") (pin "4") (pinfunction "IP+_4") (pintype "passive"))
      (node (ref "U2") (pin "4_1") (pinfunction "IP+_4_1") (pintype "passive"))
      (node (ref "U2") (pin "4_10") (pinfunction "IP+_4_10") (pintype "passive"))
      (node (ref "U2") (pin "4_11") (pinfunction "IP+_4_11") (pintype "passive"))
      (node (ref "U2") (pin "4_12") (pinfunction "IP+_4_12") (pintype "passive"))
      (node (ref "U2") (pin "4_13") (pinfunction "IP+_4_13") (pintype "passive"))
      (node (ref "U2") (pin "4_14") (pinfunction "IP+_4_14") (pintype "passive"))
      (node (ref "U2") (pin "4_15") (pinfunction "IP+_4_15") (pintype "passive"))
      (node (ref "U2") (pin "4_16") (pinfunction "IP+_4_16") (pintype "passive"))
      (node (ref "U2") (pin "4_2") (pinfunction "IP+_4_2") (pintype "passive"))
      (node (ref "U2") (pin "4_3") (pinfunction "IP+_4_3") (pintype "passive"))
      (node (ref "U2") (pin "4_4") (pinfunction "IP+_4_4") (pintype "passive"))
      (node (ref "U2") (pin "4_5") (pinfunction "IP+_4_5") (pintype "passive"))
      (node (ref "U2") (pin "4_6") (pinfunction "IP+_4_6") (pintype "passive"))
      (node (ref "U2") (pin "4_7") (pinfunction "IP+_4_7") (pintype "passive"))
      (node (ref "U2") (pin "4_8") (pinfunction "IP+_4_8") (pintype "passive"))
      (node (ref "U2") (pin "4_9") (pinfunction "IP+_4_9") (pintype "passive"))
    )
    (net (code "13") (name "/I_OUT1") (class "Default")
      (node (ref "U1") (pin "3") (pinfunction "VIOUT_3") (pintype "output"))
    )
    (net (code "14") (name "/I_OUT2") (class "Default")
      (node (ref "U2") (pin "3") (pinfunction "VIOUT_3") (pintype "output"))
    )
    (net (code "15") (name "/PWM_OUT1") (class "Default")
      (node (ref "D4") (pin "2") (pinfunction "A_2") (pintype "passive"))
      (node (ref "T6") (pin "5") (pinfunction "D_5") (pintype "passive"))
      (node (ref "T6") (pin "6") (pinfunction "D_6") (pintype "passive"))
      (node (ref "T6") (pin "7") (pinfunction "D_7") (pintype "passive"))
      (node (ref "T6") (pin "8") (pinfunction "D_8") (pintype "passive"))
      (node (ref "TRM3") (pin "1") (pinfunction "1_1") (pintype "passive"))
      (node (ref "TRM4") (pin "1") (pinfunction "1_1") (pintype "passive"))
    )
    (net (code "16") (name "/PWM_OUT2") (class "Default")
      (node (ref "D6") (pin "2") (pinfunction "A_2") (pintype "passive"))
      (node (ref "T14") (pin "5") (pinfunction "D_5") (pintype "passive"))
      (node (ref "T14") (pin "6") (pinfunction "D_6") (pintype "passive"))
      (node (ref "T14") (pin "7") (pinfunction "D_7") (pintype "passive"))
      (node (ref "T14") (pin "8") (pinfunction "D_8") (pintype "passive"))
      (node (ref "TRM7") (pin "1") (pinfunction "1_1") (pintype "passive"))
      (node (ref "TRM8") (pin "1") (pinfunction "1_1") (pintype "passive"))
    )
    (net (code "17") (name "/PWM_OUT3") (class "Default")
      (node (ref "D3") (pin "2") (pinfunction "A_2") (pintype "passive"))
      (node (ref "T5") (pin "3") (pinfunction "D_3") (pintype "passive"))
    )
    (net (code "18") (name "/PWM_OUT4") (class "Default")
      (node (ref "D5") (pin "2") (pinfunction "A_2") (pintype "passive"))
      (node (ref "T13") (pin "3") (pinfunction "D_3") (pintype "passive"))
    )
    (net (code "19") (name "/uC_AN1") (class "Default")
      (node (ref "C7") (pin "1") (pinfunction "1_1") (pintype "passive"))
      (node (ref "R8") (pin "2") (pinfunction "2_2") (pintype "passive"))
    )
    (net (code "20") (name "/uC_AN2") (class "Default")
      (node (ref "C18") (pin "1") (pinfunction "1_1") (pintype "passive"))
      (node (ref "R28") (pin "2") (pinfunction "2_2") (pintype "passive"))
    )
    (net (code "21") (name "/uC_IN1") (class "Default")
      (node (ref "R4") (pin "1") (pinfunction "1_1") (pintype "passive"))
      (node (ref "R7") (pin "2") (pinfunction "2_2") (pintype "passive"))
      (node (ref "T2") (pin "3") (pinfunction "C_3") (pintype "passive"))
    )
    (net (code "22") (name "/uC_IN2") (class "Default")
      (node (ref "R22") (pin "1") (pinfunction "1_1") (pintype "passive"))
      (node (ref "R25") (pin "2") (pinfunction "2_2") (pintype "passive"))
      (node (ref "T4") (pin "3") (pinfunction "C_3") (pintype "passive"))
    )
    (net (code "25") (name "/uC_PWM1") (class "Default")
      (node (ref "R46") (pin "1") (pinfunction "1_1") (pintype "passive"))
    )
    (net (code "26") (name "/uC_PWM2") (class "Default")
      (node (ref "R56") (pin "1") (pinfunction "1_1") (pintype "passive"))
    )
    (net (code "27") (name "/uC_PWM3") (class "Default")
      (node (ref "R45") (pin "1") (pinfunction "1_1") (pintype "passive"))
    )
    (net (code "28") (name "/uC_PWM4") (class "Default")
      (node (ref "R55") (pin "1") (pinfunction "1_1") (pintype "passive"))
    )
    (net (code "29") (name "/uC_PWM5") (class "Default")
      (node (ref "R5") (pin "2") (pinfunction "2_2") (pintype "passive"))
    )
    (net (code "30") (name "/uC_PWM6") (class "Default")
      (node (ref "R24") (pin "2") (pinfunction "2_2") (pintype "passive"))
    )
    (net (code "31") (name "GND") (class "Default")
      (node (ref "C1") (pin "2") (pinfunction "2_2") (pintype "passive"))
      (node (ref "C10") (pin "2") (pinfunction "2_2") (pintype "passive"))
      (node (ref "C12") (pin "2") (pinfunction "2_2") (pintype "passive"))
      (node (ref "C14") (pin "2") (pinfunction "2_2") (pintype "passive"))
      (node (ref "C15") (pin "2") (pinfunction "2_2") (pintype "passive"))
      (node (ref "C16") (pin "2") (pinfunction "2_2") (pintype "passive"))
      (node (ref "C18") (pin "2") (pinfunction "2_2") (pintype "passive"))
      (node (ref "C19") (pin "2") (pinfunction "2_2") (pintype "passive"))
      (node (ref "C2") (pin "2") (pinfunction "2_2") (pintype "passive"))
      (node (ref "C20") (pin "2") (pinfunction "2_2") (pintype "passive"))
      (node (ref "C21") (pin "2") (pinfunction "2_2") (pintype "passive"))
      (node (ref "C23") (pin "2") (pinfunction "2_2") (pintype "passive"))
      (node (ref "C24") (pin "2") (pinfunction "2_2") (pintype "passive"))
      (node (ref "C4") (pin "2") (pinfunction "2_2") (pintype "passive"))
      (node (ref "C5") (pin "2") (pinfunction "2_2") (pintype "passive"))
      (node (ref "C7") (pin "2") (pinfunction "2_2") (pintype "passive"))
      (node (ref "C8") (pin "2") (pinfunction "2_2") (pintype "passive"))
      (node (ref "C9") (pin "2") (pinfunction "2_2") (pintype "passive"))
      (node (ref "CI1") (pin "2") (pinfunction "GND_2") (pintype "power_in"))
      (node (ref "CI2") (pin "4") (pinfunction "GND_4") (pintype "power_in"))
      (node (ref "CI3") (pin "2") (pinfunction "GND_2") (pintype "power_in"))
      (node (ref "CI4") (pin "4") (pinfunction "GND_4") (pintype "power_in"))
      (node (ref "D1") (pin "1") (pinfunction "A_1") (pintype "passive"))
      (node (ref "D2") (pin "1") (pinfunction "A_1") (pintype "passive"))
      (node (ref "R15") (pin "1") (pinfunction "1_1") (pintype "passive"))
      (node (ref "R16") (pin "1") (pinfunction "1_1") (pintype "passive"))
      (node (ref "R18") (pin "1") (pinfunction "1_1") (pintype "passive"))
      (node (ref "R19") (pin "1") (pinfunction "1_1") (pintype "passive"))
      (node (ref "R34") (pin "1") (pinfunction "1_1") (pintype "passive"))
      (node (ref "R35") (pin "1") (pinfunction "1_1") (pintype "passive"))
      (node (ref "R36") (pin "1") (pinfunction "1_1") (pintype "passive"))
      (node (ref "R38") (pin "1") (pinfunction "1_1") (pintype "passive"))
      (node (ref "R47") (pin "1") (pinfunction "1_1") (pintype "passive"))
      (node (ref "R48") (pin "1") (pinfunction "1_1") (pintype "passive"))
      (node (ref "R57") (pin "1") (pinfunction "1_1") (pintype "passive"))
      (node (ref "R58") (pin "1") (pinfunction "1_1") (pintype "passive"))
      (node (ref "T10") (pin "3") (pinfunction "C_3") (pintype "passive"))
      (node (ref "T11") (pin "2") (pinfunction "E_2") (pintype "passive"))
      (node (ref "T12") (pin "2") (pinfunction "E_2") (pintype "passive"))
      (node (ref "T13") (pin "2") (pinfunction "S_2") (pintype "passive"))
      (node (ref "T17") (pin "3") (pinfunction "C_3") (pintype "passive"))
      (node (ref "T18") (pin "3") (pinfunction "C_3") (pintype "passive"))
      (node (ref "T19") (pin "2") (pinfunction "E_2") (pintype "passive"))
      (node (ref "T2") (pin "2") (pinfunction "E_2") (pintype "passive"))
      (node (ref "T20") (pin "2") (pinfunction "E_2") (pintype "passive"))
      (node (ref "T4") (pin "2") (pinfunction "E_2") (pintype "passive"))
      (node (ref "T5") (pin "2") (pinfunction "S_2") (pintype "passive"))
      (node (ref "T9") (pin "3") (pinfunction "C_3") (pintype "passive"))
      (node (ref "U1") (pin "2") (pinfunction "GND_2") (pintype "power_in"))
      (node (ref "U2") (pin "2") (pinfunction "GND_2") (pintype "power_in"))
    )
    (net (code "32") (name "Net-(CI1-+)") (class "Default")
      (node (ref "C4") (pin "1") (pinfunction "1_1") (pintype "passive"))
      (node (ref "CI1") (pin "3") (pinfunction "+_3") (pintype "input"))
      (node (ref "D1") (pin "3") (pinfunction "K/A_3") (pintype "passive"))
      (node (ref "R1") (pin "1") (pinfunction "1_1") (pintype "passive"))
      (node (ref "R2") (pin "1") (pinfunction "1_1") (pintype "passive"))
      (node (ref "R6") (pin "2") (pinfunction "2_2") (pintype "passive"))
    )
    (net (code "33") (name "Net-(CI1--)") (class "Default")
      (node (ref "C6") (pin "2") (pinfunction "2_2") (pintype "passive"))
      (node (ref "CI1") (pin "4") (pinfunction "-_4") (pintype "input"))
      (node (ref "R14") (pin "1") (pinfunction "1_1") (pintype "passive"))
      (node (ref "R19") (pin "2") (pinfunction "2_2") (pintype "passive"))
    )
    (net (code "34") (name "Net-(CI1-OUT)") (class "Default")
      (node (ref "C6") (pin "1") (pinfunction "1_1") (pintype "passive"))
      (node (ref "CI1") (pin "1") (pinfunction "OUT_1") (pintype "output"))
      (node (ref "R1") (pin "2") (pinfunction "2_2") (pintype "passive"))
      (node (ref "R14") (pin "2") (pinfunction "2_2") (pintype "passive"))
      (node (ref "R8") (pin "1") (pinfunction "1_1") (pintype "passive"))
    )
    (net (code "35") (name "Net-(CI2A--)") (class "Default")
      (node (ref "C11") (pin "2") (pinfunction "2_2") (pintype "passive"))
      (node (ref "CI2") (pin "2") (pinfunction "-_2") (pintype "input"))
      (node (ref "R16") (pin "2") (pinfunction "2_2") (pintype "passive"))
      (node (ref "R17") (pin "1") (pinfunction "1_1") (pintype "passive"))
    )
    (net (code "36") (name "Net-(CI2A-OUT)") (class "Default")
      (node (ref "C11") (pin "1") (pinfunction "1_1") (pintype "passive"))
      (node (ref "CI2") (pin "1") (pinfunction "OUT_1") (pintype "output"))
      (node (ref "R17") (pin "2") (pinfunction "2_2") (pintype "passive"))
      (node (ref "R9") (pin "1") (pinfunction "1_1") (pintype "passive"))
    )
    (net (code "37") (name "Net-(CI2B-+)") (class "Default")
      (node (ref "C9") (pin "1") (pinfunction "1_1") (pintype "passive"))
      (node (ref "CI2") (pin "5") (pinfunction "+_5") (pintype "input"))
      (node (ref "R9") (pin "2") (pinfunction "2_2") (pintype "passive"))
    )
    (net (code "38") (name "Net-(CI2B--)") (class "Default")
      (node (ref "CI2") (pin "6") (pinfunction "-_6") (pintype "input"))
      (node (ref "CI2") (pin "7") (pinfunction "OUT_7") (pintype "output"))
      (node (ref "R13") (pin "2") (pinfunction "2_2") (pintype "passive"))
    )
    (net (code "39") (name "Net-(CI3-+)") (class "Default")
      (node (ref "C15") (pin "1") (pinfunction "1_1") (pintype "passive"))
      (node (ref "CI3") (pin "3") (pinfunction "+_3") (pintype "input"))
      (node (ref "D2") (pin "3") (pinfunction "K/A_3") (pintype "passive"))
      (node (ref "R20") (pin "1") (pinfunction "1_1") (pintype "passive"))
      (node (ref "R23") (pin "1") (pinfunction "1_1") (pintype "passive"))
      (node (ref "R26") (pin "2") (pinfunction "2_2") (pintype "passive"))
    )
    (net (code "40") (name "Net-(CI3--)") (class "Default")
      (node (ref "C17") (pin "2") (pinfunction "2_2") (pintype "passive"))
      (node (ref "CI3") (pin "4") (pinfunction "-_4") (pintype "input"))
      (node (ref "R33") (pin "1") (pinfunction "1_1") (pintype "passive"))
      (node (ref "R38") (pin "2") (pinfunction "2_2") (pintype "passive"))
    )
    (net (code "41") (name "Net-(CI3-OUT)") (class "Default")
      (node (ref "C17") (pin "1") (pinfunction "1_1") (pintype "passive"))
      (node (ref "CI3") (pin "1") (pinfunction "OUT_1") (pintype "output"))
      (node (ref "R20") (pin "2") (pinfunction "2_2") (pintype "passive"))
      (node (ref "R28") (pin "1") (pinfunction "1_1") (pintype "passive"))
      (node (ref "R33") (pin "2") (pinfunction "2_2") (pintype "passive"))
    )
    (net (code "42") (name "Net-(CI4A--)") (class "Default")
      (node (ref "C22") (pin "2") (pinfunction "2_2") (pintype "passive"))
      (node (ref "CI4") (pin "2") (pinfunction "-_2") (pintype "input"))
      (node (ref "R36") (pin "2") (pinfunction "2_2") (pintype "passive"))
      (node (ref "R37") (pin "1") (pinfunction "1_1") (pintype "passive"))
    )
    (net (code "43") (name "Net-(CI4A-OUT)") (class "Default")
      (node (ref "C22") (pin "1") (pinfunction "1_1") (pintype "passive"))
      (node (ref "CI4") (pin "1") (pinfunction "OUT_1") (pintype "output"))
      (node (ref "R29") (pin "1") (pinfunction "1_1") (pintype "passive"))
      (node (ref "R37") (pin "2") (pinfunction "2_2") (pintype "passive"))
    )
    (net (code "44") (name "Net-(CI4B-+)") (class "Default")
      (node (ref "C20") (pin "1") (pinfunction "1_1") (pintype "passive"))
      (node (ref "CI4") (pin "5") (pinfunction "+_5") (pintype "input"))
      (node (ref "R29") (pin "2") (pinfunction "2_2") (pintype "passive"))
    )
    (net (code "45") (name "Net-(CI4B--)") (class "Default")
      (node (ref "CI4") (pin "6") (pinfunction "-_6") (pintype "input"))
      (node (ref "CI4") (pin "7") (pinfunction "OUT_7") (pintype "output"))
      (node (ref "R32") (pin "2") (pinfunction "2_2") (pintype "passive"))
    )
    (net (code "46") (name "Net-(T1-B)") (class "Default")
      (node (ref "C3") (pin "2") (pinfunction "2_2") (pintype "passive"))
      (node (ref "R10") (pin "1") (pinfunction "1_1") (pintype "passive"))
      (node (ref "R11") (pin "1") (pinfunction "1_1") (pintype "passive"))
      (node (ref "R3") (pin "1") (pinfunction "1_1") (pintype "passive"))
      (node (ref "T1") (pin "1") (pinfunction "B_1") (pintype "passive"))
    )
    (net (code "47") (name "Net-(T1-E)") (class "Default")
      (node (ref "R11") (pin "2") (pinfunction "2_2") (pintype "passive"))
      (node (ref "R12") (pin "1") (pinfunction "1_1") (pintype "passive"))
      (node (ref "R18") (pin "2") (pinfunction "2_2") (pintype "passive"))
      (node (ref "T1") (pin "2") (pinfunction "E_2") (pintype "passive"))
    )
    (net (code "48") (name "Net-(T2-B)") (class "Default")
      (node (ref "R12") (pin "2") (pinfunction "2_2") (pintype "passive"))
      (node (ref "R7") (pin "1") (pinfunction "1_1") (pintype "passive"))
      (node (ref "T2") (pin "1") (pinfunction "B_1") (pintype "passive"))
    )
    (net (code "49") (name "Net-(T3-B)") (class "Default")
      (node (ref "C13") (pin "2") (pinfunction "2_2") (pintype "passive"))
      (node (ref "R21") (pin "1") (pinfunction "1_1") (pintype "passive"))
      (node (ref "R27") (pin "1") (pinfunction "1_1") (pintype "passive"))
      (node (ref "R30") (pin "1") (pinfunction "1_1") (pintype "passive"))
      (node (ref "T3") (pin "1") (pinfunction "B_1") (pintype "passive"))
    )
    (net (code "50") (name "Net-(T3-E)") (class "Default")
      (node (ref "R30") (pin "2") (pinfunction "2_2") (pintype "passive"))
      (node (ref "R31") (pin "1") (pinfunction "1_1") (pintype "passive"))
      (node (ref "R35") (pin "2") (pinfunction "2_2") (pintype "passive"))
      (node (ref "T3") (pin "2") (pinfunction "E_2") (pintype "passive"))
    )
    (net (code "51") (name "Net-(T4-B)") (class "Default")
      (node (ref "R25") (pin "1") (pinfunction "1_1") (pintype "passive"))
      (node (ref "R31") (pin "2") (pinfunction "2_2") (pintype "passive"))
      (node (ref "T4") (pin "1") (pinfunction "B_1") (pintype "passive"))
    )
    (net (code "52") (name "Net-(T5-G)") (class "Default")
      (node (ref "R41") (pin "2") (pinfunction "2_2") (pintype "passive"))
      (node (ref "T5") (pin "1") (pinfunction "G_1") (pintype "passive"))
    )
    (net (code "53") (name "Net-(T6-G)") (class "Default")
      (node (ref "R42") (pin "2") (pinfunction "2_2") (pintype "passive"))
      (node (ref "T6") (pin "4") (pinfunction "G_4") (pintype "passive"))
    )
    (net (code "54") (name "Net-(T7-B)") (class "Default")
      (node (ref "R39") (pin "1") (pinfunction "1_1") (pintype "passive"))
      (node (ref "R43") (pin "2") (pinfunction "2_2") (pintype "passive"))
      (node (ref "T7") (pin "1") (pinfunction "B_1") (pintype "passive"))
      (node (ref "T9") (pin "1") (pinfunction "B_1") (pintype "passive"))
    )
    (net (code "55") (name "Net-(T7-E)") (class "Default")
      (node (ref "R41") (pin "1") (pinfunction "1_1") (pintype "passive"))
      (node (ref "T7") (pin "2") (pinfunction "E_2") (pintype "passive"))
      (node (ref "T9") (pin "2") (pinfunction "E_2") (pintype "passive"))
    )
    (net (code "56") (name "Net-(T10-B)") (class "Default")
      (node (ref "R40") (pin "1") (pinfunction "1_1") (pintype "passive"))
      (node (ref "R44") (pin "2") (pinfunction "2_2") (pintype "passive"))
      (node (ref "T10") (pin "1") (pinfunction "B_1") (pintype "passive"))
      (node (ref "T8") (pin "1") (pinfunction "B_1") (pintype "passive"))
    )
    (net (code "57") (name "Net-(T10-E)") (class "Default")
      (node (ref "R42") (pin "1") (pinfunction "1_1") (pintype "passive"))
      (node (ref "T10") (pin "2") (pinfunction "E_2") (pintype "passive"))
      (node (ref "T8") (pin "2") (pinfunction "E_2") (pintype "passive"))
    )
    (net (code "58") (name "Net-(T11-B)") (class "Default")
      (node (ref "R45") (pin "2") (pinfunction "2_2") (pintype "passive"))
      (node (ref "R47") (pin "2") (pinfunction "2_2") (pintype "passive"))
      (node (ref "T11") (pin "1") (pinfunction "B_1") (pintype "passive"))
    )
    (net (code "59") (name "Net-(T11-C)") (class "Default")
      (node (ref "R43") (pin "1") (pinfunction "1_1") (pintype "passive"))
      (node (ref "T11") (pin "3") (pinfunction "C_3") (pintype "passive"))
    )
    (net (code "60") (name "Net-(T12-B)") (class "Default")
      (node (ref "R46") (pin "2") (pinfunction "2_2") (pintype "passive"))
      (node (ref "R48") (pin "2") (pinfunction "2_2") (pintype "passive"))
      (node (ref "T12") (pin "1") (pinfunction "B_1") (pintype "passive"))
    )
    (net (code "61") (name "Net-(T12-C)") (class "Default")
      (node (ref "R44") (pin "1") (pinfunction "1_1") (pintype "passive"))
      (node (ref "T12") (pin "3") (pinfunction "C_3") (pintype "passive"))
    )
    (net (code "62") (name "Net-(T13-G)") (class "Default")
      (node (ref "R51") (pin "2") (pinfunction "2_2") (pintype "passive"))
      (node (ref "T13") (pin "1") (pinfunction "G_1") (pintype "passive"))
    )
    (net (code "63") (name "Net-(T14-G)") (class "Default")
      (node (ref "R52") (pin "2") (pinfunction "2_2") (pintype "passive"))
      (node (ref "T14") (pin "4") (pinfunction "G_4") (pintype "passive"))
    )
    (net (code "64") (name "Net-(T15-B)") (class "Default")
      (node (ref "R49") (pin "1") (pinfunction "1_1") (pintype "passive"))
      (node (ref "R53") (pin "2") (pinfunction "2_2") (pintype "passive"))
      (node (ref "T15") (pin "1") (pinfunction "B_1") (pintype "passive"))
      (node (ref "T17") (pin "1") (pinfunction "B_1") (pintype "passive"))
    )
    (net (code "65") (name "Net-(T15-E)") (class "Default")
      (node (ref "R51") (pin "1") (pinfunction "1_1") (pintype "passive"))
      (node (ref "T15") (pin "2") (pinfunction "E_2") (pintype "passive"))
      (node (ref "T17") (pin "2") (pinfunction "E_2") (pintype "passive"))
    )
    (net (code "66") (name "Net-(T16-B)") (class "Default")
      (node (ref "R50") (pin "1") (pinfunction "1_1") (pintype "passive"))
      (node (ref "R54") (pin "2") (pinfunction "2_2") (pintype "passive"))
      (node (ref "T16") (pin "1") (pinfunction "B_1") (pintype "passive"))
      (node (ref "T18") (pin "1") (pinfunction "B_1") (pintype "passive"))
    )
    (net (code "67") (name "Net-(T16-E)") (class "Default")
      (node (ref "R52") (pin "1") (pinfunction "1_1") (pintype "passive"))
      (node (ref "T16") (pin "2") (pinfunction "E_2") (pintype "passive"))
      (node (ref "T18") (pin "2") (pinfunction "E_2") (pintype "passive"))
    )
    (net (code "68") (name "Net-(T19-B)") (class "Default")
      (node (ref "R55") (pin "2") (pinfunction "2_2") (pintype "passive"))
      (node (ref "R57") (pin "2") (pinfunction "2_2") (pintype "passive"))
      (node (ref "T19") (pin "1") (pinfunction "B_1") (pintype "passive"))
    )
    (net (code "69") (name "Net-(T19-C)") (class "Default")
      (node (ref "R53") (pin "1") (pinfunction "1_1") (pintype "passive"))
      (node (ref "T19") (pin "3") (pinfunction "C_3") (pintype "passive"))
    )
    (net (code "70") (name "Net-(T20-B)") (class "Default")
      (node (ref "R56") (pin "2") (pinfunction "2_2") (pintype "passive"))
      (node (ref "R58") (pin "2") (pinfunction "2_2") (pintype "passive"))
      (node (ref "T20") (pin "1") (pinfunction "B_1") (pintype "passive"))
    )
    (net (code "71") (name "Net-(T20-C)") (class "Default")
      (node (ref "R54") (pin "1") (pinfunction "1_1") (pintype "passive"))
      (node (ref "T20") (pin "3") (pinfunction "C_3") (pintype "passive"))
    )
    (net (code "72") (name "VCC") (class "Default")
      (node (ref "D3") (pin "1") (pinfunction "K_1") (pintype "passive"))
      (node (ref "D5") (pin "1") (pinfunction "K_1") (pintype "passive"))
    )
    (net (code "73") (name "VCC1") (class "Default")
      (node (ref "D4") (pin "1") (pinfunction "K_1") (pintype "passive"))
      (node (ref "R40") (pin "2") (pinfunction "2_2") (pintype "passive"))
      (node (ref "T8") (pin "3") (pinfunction "C_3") (pintype "passive"))
      (node (ref "TRM1") (pin "1") (pinfunction "1_1") (pintype "passive"))
      (node (ref "TRM2") (pin "1") (pinfunction "1_1") (pintype "passive"))
    )
    (net (code "74") (name "VCC2") (class "Default")
      (node (ref "D6") (pin "1") (pinfunction "K_1") (pintype "passive"))
      (node (ref "R50") (pin "2") (pinfunction "2_2") (pintype "passive"))
      (node (ref "T16") (pin "3") (pinfunction "C_3") (pintype "passive"))
      (node (ref "TRM5") (pin "1") (pinfunction "1_1") (pintype "passive"))
      (node (ref "TRM6") (pin "1") (pinfunction "1_1") (pintype "passive"))
    )
    (net (code "75") (name "power_GND1") (class "Default")
      (node (ref "TRM11") (pin "1") (pinfunction "1_1") (pintype "passive"))
      (node (ref "TRM9") (pin "1") (pinfunction "1_1") (pintype "passive"))
      (node (ref "U1") (pin "5") (pinfunction "IP-_5") (pintype "passive"))
      (node (ref "U1") (pin "5_1") (pinfunction "IP-_5_1") (pintype "passive"))
      (node (ref "U1") (pin "5_10") (pinfunction "IP-_5_10") (pintype "passive"))
      (node (ref "U1") (pin "5_11") (pinfunction "IP-_5_11") (pintype "passive"))
      (node (ref "U1") (pin "5_12") (pinfunction "IP-_5_12") (pintype "passive"))
      (node (ref "U1") (pin "5_13") (pinfunction "IP-_5_13") (pintype "passive"))
      (node (ref "U1") (pin "5_14") (pinfunction "IP-_5_14") (pintype "passive"))
      (node (ref "U1") (pin "5_15") (pinfunction "IP-_5_15") (pintype "passive"))
      (node (ref "U1") (pin "5_16") (pinfunction "IP-_5_16") (pintype "passive"))
      (node (ref "U1") (pin "5_2") (pinfunction "IP-_5_2") (pintype "passive"))
      (node (ref "U1") (pin "5_3") (pinfunction "IP-_5_3") (pintype "passive"))
      (node (ref "U1") (pin "5_4") (pinfunction "IP-_5_4") (pintype "passive"))
      (node (ref "U1") (pin "5_5") (pinfunction "IP-_5_5") (pintype "passive"))
      (node (ref "U1") (pin "5_6") (pinfunction "IP-_5_6") (pintype "passive"))
      (node (ref "U1") (pin "5_7") (pinfunction "IP-_5_7") (pintype "passive"))
      (node (ref "U1") (pin "5_8") (pinfunction "IP-_5_8") (pintype "passive"))
      (node (ref "U1") (pin "5_9") (pinfunction "IP-_5_9") (pintype "passive"))
    )
    (net (code "76") (name "power_GND2") (class "Default")
      (node (ref "TRM10") (pin "1") (pinfunction "1_1") (pintype "passive"))
      (node (ref "TRM12") (pin "1") (pinfunction "1_1") (pintype "passive"))
      (node (ref "U2") (pin "5") (pinfunction "IP-_5") (pintype "passive"))
      (node (ref "U2") (pin "5_1") (pinfunction "IP-_5_1") (pintype "passive"))
      (node (ref "U2") (pin "5_10") (pinfunction "IP-_5_10") (pintype "passive"))
      (node (ref "U2") (pin "5_11") (pinfunction "IP-_5_11") (pintype "passive"))
      (node (ref "U2") (pin "5_12") (pinfunction "IP-_5_12") (pintype "passive"))
      (node (ref "U2") (pin "5_13") (pinfunction "IP-_5_13") (pintype "passive"))
      (node (ref "U2") (pin "5_14") (pinfunction "IP-_5_14") (pintype "passive"))
      (node (ref "U2") (pin "5_15") (pinfunction "IP-_5_15") (pintype "passive"))
      (node (ref "U2") (pin "5_16") (pinfunction "IP-_5_16") (pintype "passive"))
      (node (ref "U2") (pin "5_2") (pinfunction "IP-_5_2") (pintype "passive"))
      (node (ref "U2") (pin "5_3") (pinfunction "IP-_5_3") (pintype "passive"))
      (node (ref "U2") (pin "5_4") (pinfunction "IP-_5_4") (pintype "passive"))
      (node (ref "U2") (pin "5_5") (pinfunction "IP-_5_5") (pintype "passive"))
      (node (ref "U2") (pin "5_6") (pinfunction "IP-_5_6") (pintype "passive"))
      (node (ref "U2") (pin "5_7") (pinfunction "IP-_5_7") (pintype "passive"))
      (node (ref "U2") (pin "5_8") (pinfunction "IP-_5_8") (pintype "passive"))
      (node (ref "U2") (pin "5_9") (pinfunction "IP-_5_9") (pintype "passive"))
    )
  )
)
